# Power_Distro_Board_V6.net
KiCad netlist of a schematic drawn in EAGLE
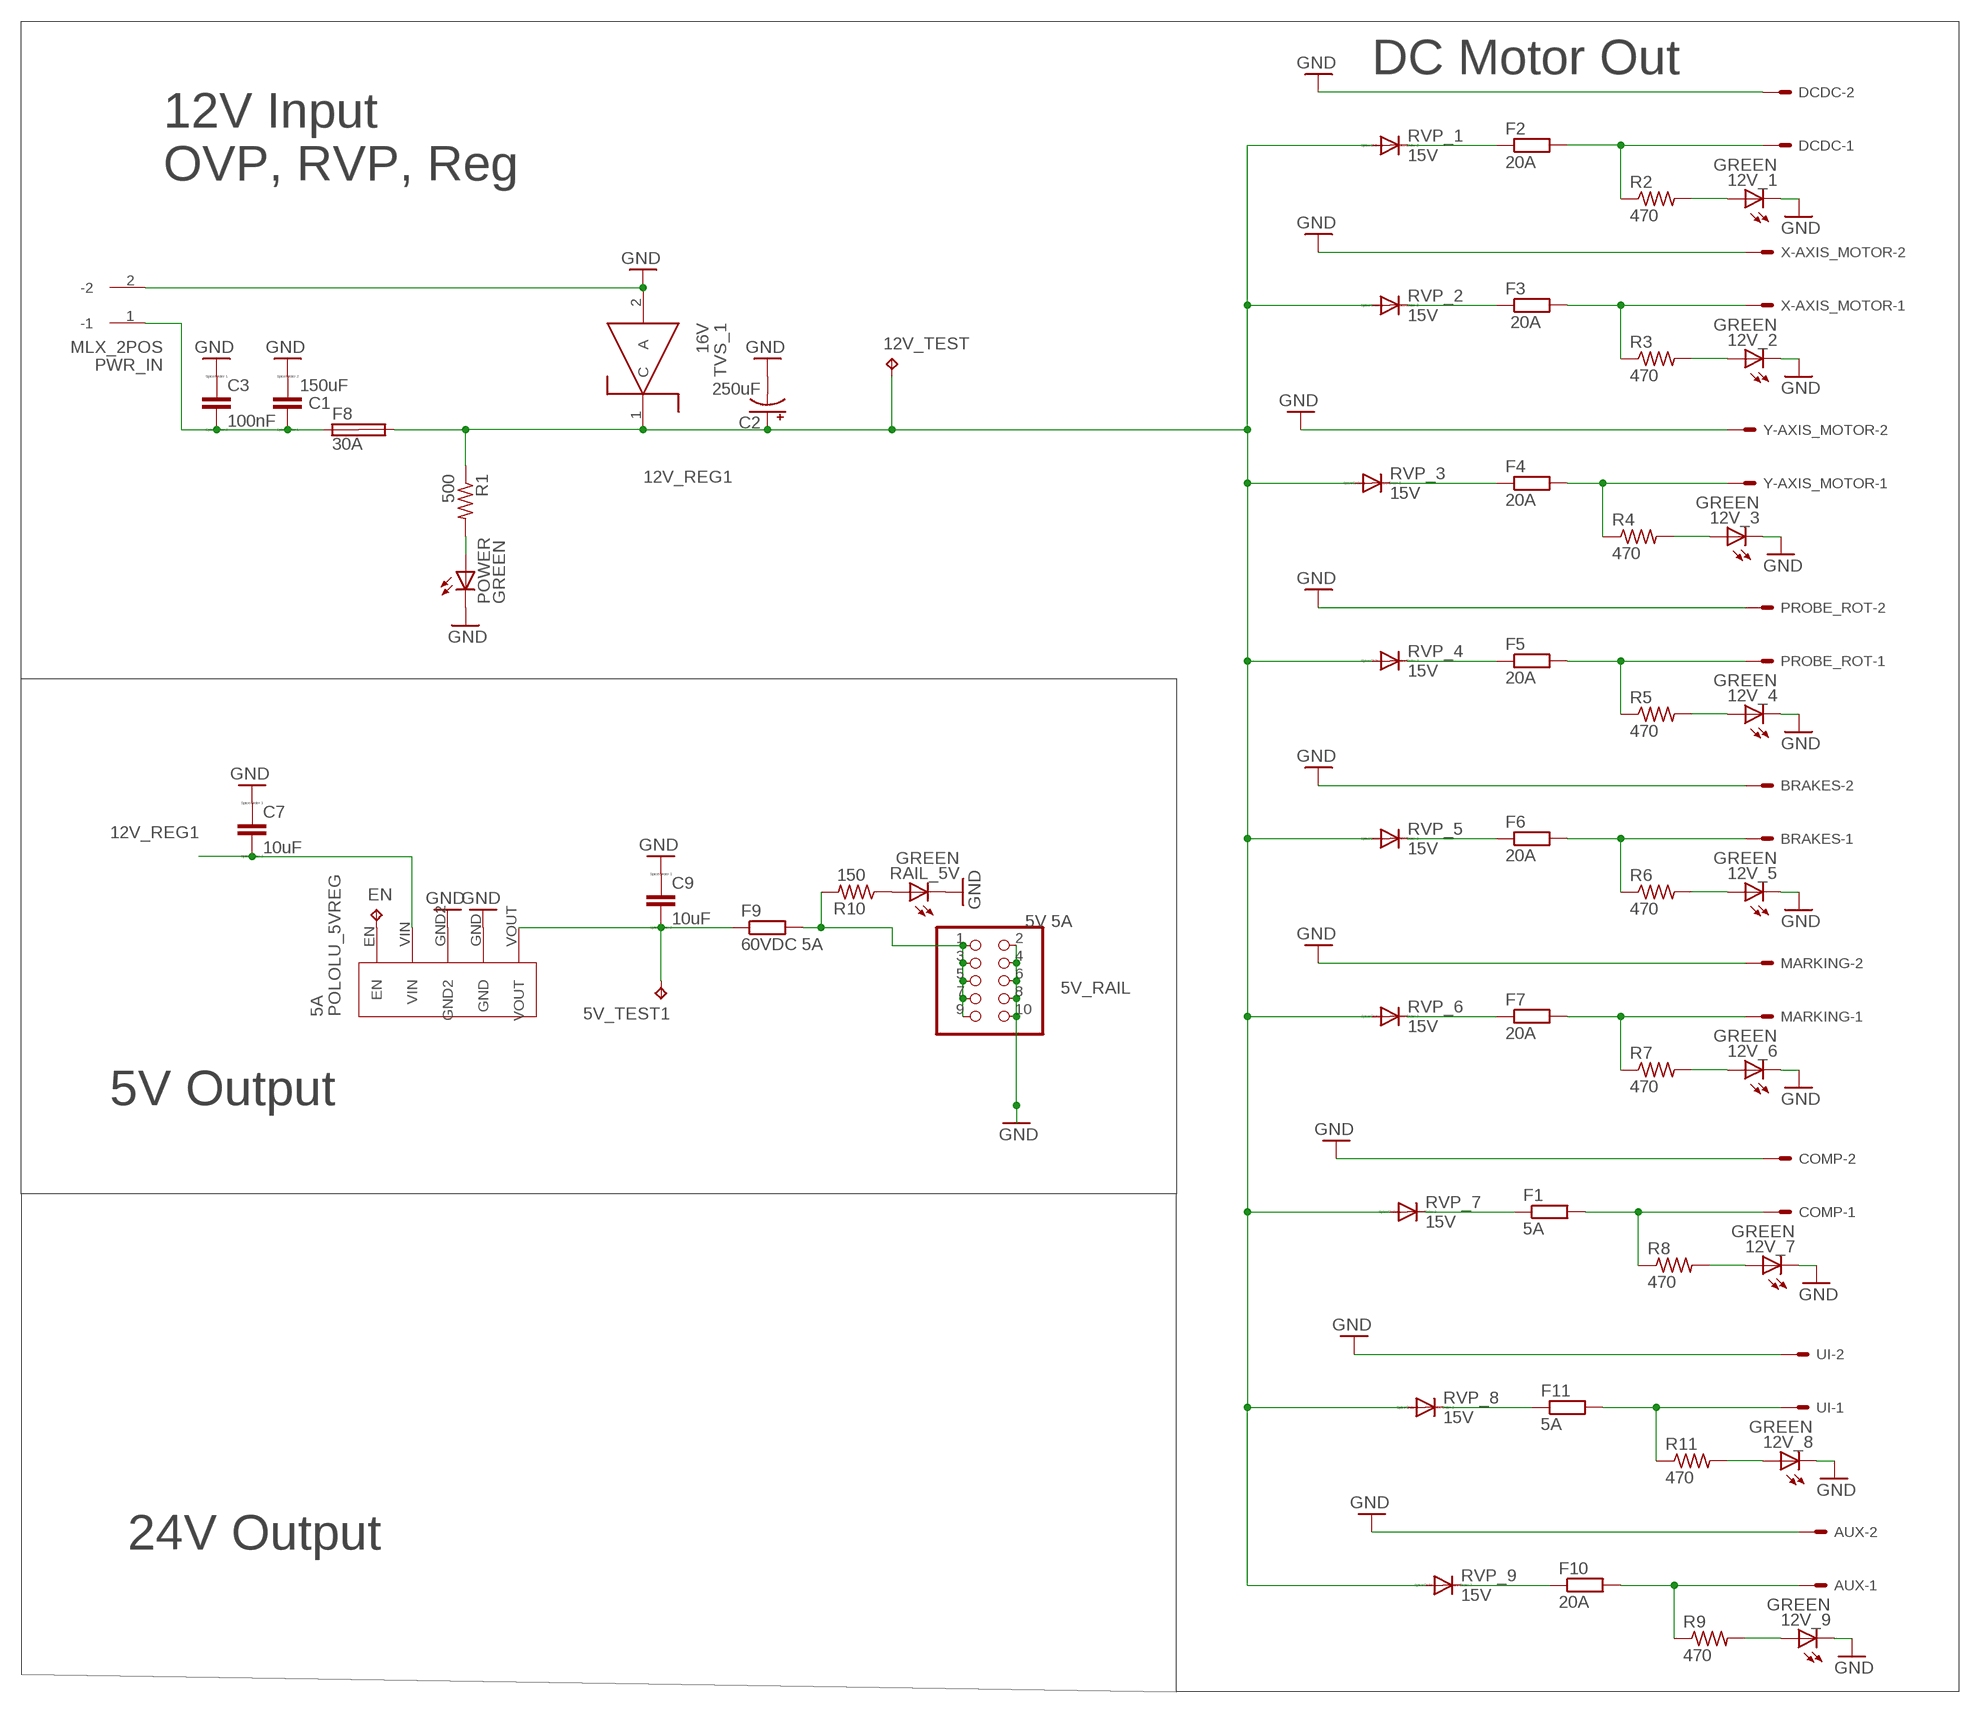
[diagram p0: schematic, sheet 1]

(export (version "E")
  (design (tool "Eeschema 10.0.6"))
  (components
    (comp (ref "5A")
      (value "POLOLU_5VREG")
      (footprint "eagle-import:SIP5")
      (libsource (lib "eagle-import") (part "POLOLU_5VREG"))
    )
    (comp (ref "5V_RAIL")
      (value "5V 5A")
      (footprint "eagle-import:2X05")
      (libsource (lib "eagle-import") (part "PINHD-2X5"))
    )
    (comp (ref "5V_TEST1")
      (value "TPPAD1-13")
      (footprint "eagle-import:P1-13")
      (libsource (lib "eagle-import") (part "TPPAD1-13"))
    )
    (comp (ref "12V_1")
      (value "GREEN")
      (footprint "eagle-import:SML1206")
      (libsource (lib "eagle-import") (part "LEDSML1206"))
    )
    (comp (ref "12V_2")
      (value "GREEN")
      (footprint "eagle-import:SML1206")
      (libsource (lib "eagle-import") (part "LEDSML1206"))
    )
    (comp (ref "12V_3")
      (value "GREEN")
      (footprint "eagle-import:SML1206")
      (libsource (lib "eagle-import") (part "LEDSML1206"))
    )
    (comp (ref "12V_4")
      (value "GREEN")
      (footprint "eagle-import:SML1206")
      (libsource (lib "eagle-import") (part "LEDSML1206"))
    )
    (comp (ref "12V_5")
      (value "GREEN")
      (footprint "eagle-import:SML1206")
      (libsource (lib "eagle-import") (part "LEDSML1206"))
    )
    (comp (ref "12V_6")
      (value "GREEN")
      (footprint "eagle-import:SML1206")
      (libsource (lib "eagle-import") (part "LEDSML1206"))
    )
    (comp (ref "12V_7")
      (value "GREEN")
      (footprint "eagle-import:SML1206")
      (libsource (lib "eagle-import") (part "LEDSML1206"))
    )
    (comp (ref "12V_8")
      (value "GREEN")
      (footprint "eagle-import:SML1206")
      (libsource (lib "eagle-import") (part "LEDSML1206"))
    )
    (comp (ref "12V_9")
      (value "GREEN")
      (footprint "eagle-import:SML1206")
      (libsource (lib "eagle-import") (part "LEDSML1206"))
    )
    (comp (ref "12V_TEST")
      (value "TPPAD1-13")
      (footprint "eagle-import:P1-13")
      (libsource (lib "eagle-import") (part "TPPAD1-13"))
    )
    (comp (ref "AUX")
      (value "555X-2V")
      (footprint "eagle-import:5566-2")
      (libsource (lib "eagle-import") (part "555X-2V"))
    )
    (comp (ref "BRAKES")
      (value "555X-2V")
      (footprint "eagle-import:5566-2")
      (libsource (lib "eagle-import") (part "555X-2V"))
    )
    (comp (ref "C1")
      (value "150uF")
      (footprint "eagle-import:C1210")
      (libsource (lib "eagle-import") (part "CC1210"))
    )
    (comp (ref "C2")
      (value "250uF")
      (footprint "eagle-import:CPOL-RADIAL-5MM-10MM")
      (libsource (lib "eagle-import") (part "ALUM_ELEC_RADIAL"))
    )
    (comp (ref "C3")
      (value "100nF")
      (footprint "eagle-import:C1210")
      (libsource (lib "eagle-import") (part "CC1210"))
    )
    (comp (ref "C7")
      (value "10uF")
      (footprint "eagle-import:C1210")
      (libsource (lib "eagle-import") (part "CC1210"))
    )
    (comp (ref "C9")
      (value "10uF")
      (footprint "eagle-import:C1210")
      (libsource (lib "eagle-import") (part "CC1210"))
    )
    (comp (ref "COMP")
      (value "555X-2V")
      (footprint "eagle-import:5566-2")
      (libsource (lib "eagle-import") (part "555X-2V"))
    )
    (comp (ref "DCDC")
      (value "555X-2V")
      (footprint "eagle-import:5566-2")
      (libsource (lib "eagle-import") (part "555X-2V"))
    )
    (comp (ref "EN")
      (value "TPPAD1-13")
      (footprint "eagle-import:P1-13")
      (libsource (lib "eagle-import") (part "TPPAD1-13"))
    )
    (comp (ref "F1")
      (value "5A")
      (footprint "eagle-import:M1206")
      (libsource (lib "eagle-import") (part "R-EU_M1206"))
    )
    (comp (ref "F2")
      (value "20A")
      (footprint "eagle-import:M1206")
      (libsource (lib "eagle-import") (part "R-EU_M1206"))
    )
    (comp (ref "F3")
      (value "20A")
      (footprint "eagle-import:M1206")
      (libsource (lib "eagle-import") (part "R-EU_M1206"))
    )
    (comp (ref "F4")
      (value "20A")
      (footprint "eagle-import:M1206")
      (libsource (lib "eagle-import") (part "R-EU_M1206"))
    )
    (comp (ref "F5")
      (value "20A")
      (footprint "eagle-import:M1206")
      (libsource (lib "eagle-import") (part "R-EU_M1206"))
    )
    (comp (ref "F6")
      (value "20A")
      (footprint "eagle-import:M1206")
      (libsource (lib "eagle-import") (part "R-EU_M1206"))
    )
    (comp (ref "F7")
      (value "20A")
      (footprint "eagle-import:M1206")
      (libsource (lib "eagle-import") (part "R-EU_M1206"))
    )
    (comp (ref "F8")
      (value "30A")
      (footprint "eagle-import:SHK20L")
      (libsource (lib "eagle-import") (part "SHK20L"))
    )
    (comp (ref "F9")
      (value "60VDC 5A")
      (footprint "eagle-import:M1206")
      (libsource (lib "eagle-import") (part "R-EU_M1206"))
    )
    (comp (ref "F10")
      (value "20A")
      (footprint "eagle-import:M1206")
      (libsource (lib "eagle-import") (part "R-EU_M1206"))
    )
    (comp (ref "F11")
      (value "5A")
      (footprint "eagle-import:M1206")
      (libsource (lib "eagle-import") (part "R-EU_M1206"))
    )
    (comp (ref "MARKING")
      (value "555X-2V")
      (footprint "eagle-import:5566-2")
      (libsource (lib "eagle-import") (part "555X-2V"))
    )
    (comp (ref "POWER")
      (value "GREEN")
      (footprint "eagle-import:SML1206")
      (libsource (lib "eagle-import") (part "LEDSML1206"))
    )
    (comp (ref "PROBE_ROT")
      (value "555X-2V")
      (footprint "eagle-import:5566-2")
      (libsource (lib "eagle-import") (part "555X-2V"))
    )
    (comp (ref "PWR_IN")
      (value "MLX_2POS")
      (footprint "eagle-import:.084MLX")
      (libsource (lib "eagle-import") (part "MLX_2POS"))
    )
    (comp (ref "R1")
      (value "500")
      (footprint "eagle-import:R1206")
      (libsource (lib "eagle-import") (part "R-US_R1206"))
    )
    (comp (ref "R2")
      (value "470")
      (footprint "eagle-import:R1206")
      (libsource (lib "eagle-import") (part "R-US_R1206"))
    )
    (comp (ref "R3")
      (value "470")
      (footprint "eagle-import:R1206")
      (libsource (lib "eagle-import") (part "R-US_R1206"))
    )
    (comp (ref "R4")
      (value "470")
      (footprint "eagle-import:R1206")
      (libsource (lib "eagle-import") (part "R-US_R1206"))
    )
    (comp (ref "R5")
      (value "470")
      (footprint "eagle-import:R1206")
      (libsource (lib "eagle-import") (part "R-US_R1206"))
    )
    (comp (ref "R6")
      (value "470")
      (footprint "eagle-import:R1206")
      (libsource (lib "eagle-import") (part "R-US_R1206"))
    )
    (comp (ref "R7")
      (value "470")
      (footprint "eagle-import:R1206")
      (libsource (lib "eagle-import") (part "R-US_R1206"))
    )
    (comp (ref "R8")
      (value "470")
      (footprint "eagle-import:R1206")
      (libsource (lib "eagle-import") (part "R-US_R1206"))
    )
    (comp (ref "R9")
      (value "470")
      (footprint "eagle-import:R1206")
      (libsource (lib "eagle-import") (part "R-US_R1206"))
    )
    (comp (ref "R10")
      (value "150")
      (footprint "eagle-import:R1206")
      (libsource (lib "eagle-import") (part "R-US_R1206"))
    )
    (comp (ref "R11")
      (value "470")
      (footprint "eagle-import:R1206")
      (libsource (lib "eagle-import") (part "R-US_R1206"))
    )
    (comp (ref "RAIL_5V")
      (value "GREEN")
      (footprint "eagle-import:SML1206")
      (libsource (lib "eagle-import") (part "LEDSML1206"))
    )
    (comp (ref "RVP_1")
      (value "15V")
      (footprint "eagle-import:TO220ACS")
      (libsource (lib "eagle-import") (part "BYT08P"))
    )
    (comp (ref "RVP_2")
      (value "15V")
      (footprint "eagle-import:TO220ACS")
      (libsource (lib "eagle-import") (part "BYT08P"))
    )
    (comp (ref "RVP_3")
      (value "15V")
      (footprint "eagle-import:TO220ACS")
      (libsource (lib "eagle-import") (part "BYT08P"))
    )
    (comp (ref "RVP_4")
      (value "15V")
      (footprint "eagle-import:TO220ACS")
      (libsource (lib "eagle-import") (part "BYT08P"))
    )
    (comp (ref "RVP_5")
      (value "15V")
      (footprint "eagle-import:TO220ACS")
      (libsource (lib "eagle-import") (part "BYT08P"))
    )
    (comp (ref "RVP_6")
      (value "15V")
      (footprint "eagle-import:TO220ACS")
      (libsource (lib "eagle-import") (part "BYT08P"))
    )
    (comp (ref "RVP_7")
      (value "15V")
      (footprint "eagle-import:TO220ACS")
      (libsource (lib "eagle-import") (part "BYT08P"))
    )
    (comp (ref "RVP_8")
      (value "15V")
      (footprint "eagle-import:TO220ACS")
      (libsource (lib "eagle-import") (part "BYT08P"))
    )
    (comp (ref "RVP_9")
      (value "15V")
      (footprint "eagle-import:TO220ACS")
      (libsource (lib "eagle-import") (part "BYT08P"))
    )
    (comp (ref "TVS_1")
      (value "16V")
      (footprint "eagle-import:DO-214AC")
      (libsource (lib "eagle-import") (part "SMAJ26A_TVSSMA"))
    )
    (comp (ref "UI")
      (value "555X-2V")
      (footprint "eagle-import:5566-2")
      (libsource (lib "eagle-import") (part "555X-2V"))
    )
    (comp (ref "X-AXIS_MOTOR")
      (value "555X-2V")
      (footprint "eagle-import:5566-2")
      (libsource (lib "eagle-import") (part "555X-2V"))
    )
    (comp (ref "Y-AXIS_MOTOR")
      (value "555X-2V")
      (footprint "eagle-import:5566-2")
      (libsource (lib "eagle-import") (part "555X-2V"))
    )
  )
  (nets
    (net (code "1") (name "/12V_REG1") (class "Default")
      (node (ref "12V_TEST") (pin "TP") (pinfunction "TP_TP") (pintype "input"))
      (node (ref "5A") (pin "VIN") (pinfunction "VIN_VIN") (pintype "bidirectional"))
      (node (ref "C2") (pin "+") (pinfunction "+_+") (pintype "passive"))
      (node (ref "C7") (pin "2") (pinfunction "2_2") (pintype "passive"))
      (node (ref "F8") (pin "2A") (pinfunction "2A_2A") (pintype "passive"))
      (node (ref "R1") (pin "1") (pinfunction "1_1") (pintype "passive"))
      (node (ref "RVP_1") (pin "A") (pinfunction "A_A") (pintype "passive"))
      (node (ref "RVP_2") (pin "A") (pinfunction "A_A") (pintype "passive"))
      (node (ref "RVP_3") (pin "A") (pinfunction "A_A") (pintype "passive"))
      (node (ref "RVP_4") (pin "A") (pinfunction "A_A") (pintype "passive"))
      (node (ref "RVP_5") (pin "A") (pinfunction "A_A") (pintype "passive"))
      (node (ref "RVP_6") (pin "A") (pinfunction "A_A") (pintype "passive"))
      (node (ref "RVP_7") (pin "A") (pinfunction "A_A") (pintype "passive"))
      (node (ref "RVP_8") (pin "A") (pinfunction "A_A") (pintype "passive"))
      (node (ref "RVP_9") (pin "A") (pinfunction "A_A") (pintype "passive"))
      (node (ref "TVS_1") (pin "1") (pinfunction "C_1") (pintype "bidirectional"))
    )
    (net (code "2") (name "GND") (class "Default")
      (node (ref "12V_1") (pin "C") (pinfunction "C_C") (pintype "passive"))
      (node (ref "12V_2") (pin "C") (pinfunction "C_C") (pintype "passive"))
      (node (ref "12V_3") (pin "C") (pinfunction "C_C") (pintype "passive"))
      (node (ref "12V_4") (pin "C") (pinfunction "C_C") (pintype "passive"))
      (node (ref "12V_5") (pin "C") (pinfunction "C_C") (pintype "passive"))
      (node (ref "12V_6") (pin "C") (pinfunction "C_C") (pintype "passive"))
      (node (ref "12V_7") (pin "C") (pinfunction "C_C") (pintype "passive"))
      (node (ref "12V_8") (pin "C") (pinfunction "C_C") (pintype "passive"))
      (node (ref "12V_9") (pin "C") (pinfunction "C_C") (pintype "passive"))
      (node (ref "5A") (pin "GND") (pinfunction "GND_GND") (pintype "bidirectional"))
      (node (ref "5A") (pin "GND2") (pinfunction "GND2_GND2") (pintype "bidirectional"))
      (node (ref "5V_RAIL") (pin "10") (pinfunction "10_10") (pintype "passive"))
      (node (ref "5V_RAIL") (pin "2") (pinfunction "2_2") (pintype "passive"))
      (node (ref "5V_RAIL") (pin "4") (pinfunction "4_4") (pintype "passive"))
      (node (ref "5V_RAIL") (pin "6") (pinfunction "6_6") (pintype "passive"))
      (node (ref "5V_RAIL") (pin "8") (pinfunction "8_8") (pintype "passive"))
      (node (ref "AUX") (pin "2") (pinfunction "S_2") (pintype "passive"))
      (node (ref "BRAKES") (pin "2") (pinfunction "S_2") (pintype "passive"))
      (node (ref "C1") (pin "2") (pinfunction "2_2") (pintype "passive"))
      (node (ref "C2") (pin "-") (pinfunction "-_-") (pintype "passive"))
      (node (ref "C3") (pin "1") (pinfunction "1_1") (pintype "passive"))
      (node (ref "C7") (pin "1") (pinfunction "1_1") (pintype "passive"))
      (node (ref "C9") (pin "1") (pinfunction "1_1") (pintype "passive"))
      (node (ref "COMP") (pin "2") (pinfunction "S_2") (pintype "passive"))
      (node (ref "DCDC") (pin "2") (pinfunction "S_2") (pintype "passive"))
      (node (ref "MARKING") (pin "2") (pinfunction "S_2") (pintype "passive"))
      (node (ref "POWER") (pin "C") (pinfunction "C_C") (pintype "passive"))
      (node (ref "PROBE_ROT") (pin "2") (pinfunction "S_2") (pintype "passive"))
      (node (ref "PWR_IN") (pin "2") (pinfunction "-2_2") (pintype "bidirectional"))
      (node (ref "RAIL_5V") (pin "C") (pinfunction "C_C") (pintype "passive"))
      (node (ref "TVS_1") (pin "2") (pinfunction "A_2") (pintype "bidirectional"))
      (node (ref "UI") (pin "2") (pinfunction "S_2") (pintype "passive"))
      (node (ref "X-AXIS_MOTOR") (pin "2") (pinfunction "S_2") (pintype "passive"))
      (node (ref "Y-AXIS_MOTOR") (pin "2") (pinfunction "S_2") (pintype "passive"))
    )
    (net (code "3") (name "Net-(5A-PadEN)") (class "Default")
      (node (ref "5A") (pin "EN") (pinfunction "EN_EN") (pintype "bidirectional"))
      (node (ref "EN") (pin "TP") (pinfunction "TP_TP") (pintype "input"))
    )
    (net (code "4") (name "Net-(5A-PadVOUT)") (class "Default")
      (node (ref "5A") (pin "VOUT") (pinfunction "VOUT_VOUT") (pintype "bidirectional"))
      (node (ref "5V_TEST1") (pin "TP") (pinfunction "TP_TP") (pintype "input"))
      (node (ref "C9") (pin "2") (pinfunction "2_2") (pintype "passive"))
      (node (ref "F9") (pin "1") (pinfunction "1_1") (pintype "passive"))
    )
    (net (code "5") (name "Net-(5V_RAIL-Pad1)") (class "Default")
      (node (ref "5V_RAIL") (pin "1") (pinfunction "1_1") (pintype "passive"))
      (node (ref "5V_RAIL") (pin "3") (pinfunction "3_3") (pintype "passive"))
      (node (ref "5V_RAIL") (pin "5") (pinfunction "5_5") (pintype "passive"))
      (node (ref "5V_RAIL") (pin "7") (pinfunction "7_7") (pintype "passive"))
      (node (ref "5V_RAIL") (pin "9") (pinfunction "9_9") (pintype "passive"))
      (node (ref "F9") (pin "2") (pinfunction "2_2") (pintype "passive"))
      (node (ref "R10") (pin "2") (pinfunction "2_2") (pintype "passive"))
    )
    (net (code "6") (name "Net-(12V_1-PadA)") (class "Default")
      (node (ref "12V_1") (pin "A") (pinfunction "A_A") (pintype "passive"))
      (node (ref "R2") (pin "2") (pinfunction "2_2") (pintype "passive"))
    )
    (net (code "7") (name "Net-(12V_2-PadA)") (class "Default")
      (node (ref "12V_2") (pin "A") (pinfunction "A_A") (pintype "passive"))
      (node (ref "R3") (pin "2") (pinfunction "2_2") (pintype "passive"))
    )
    (net (code "8") (name "Net-(12V_3-PadA)") (class "Default")
      (node (ref "12V_3") (pin "A") (pinfunction "A_A") (pintype "passive"))
      (node (ref "R4") (pin "2") (pinfunction "2_2") (pintype "passive"))
    )
    (net (code "9") (name "Net-(12V_4-PadA)") (class "Default")
      (node (ref "12V_4") (pin "A") (pinfunction "A_A") (pintype "passive"))
      (node (ref "R5") (pin "2") (pinfunction "2_2") (pintype "passive"))
    )
    (net (code "10") (name "Net-(12V_5-PadA)") (class "Default")
      (node (ref "12V_5") (pin "A") (pinfunction "A_A") (pintype "passive"))
      (node (ref "R6") (pin "2") (pinfunction "2_2") (pintype "passive"))
    )
    (net (code "11") (name "Net-(12V_6-PadA)") (class "Default")
      (node (ref "12V_6") (pin "A") (pinfunction "A_A") (pintype "passive"))
      (node (ref "R7") (pin "2") (pinfunction "2_2") (pintype "passive"))
    )
    (net (code "12") (name "Net-(12V_7-PadA)") (class "Default")
      (node (ref "12V_7") (pin "A") (pinfunction "A_A") (pintype "passive"))
      (node (ref "R8") (pin "2") (pinfunction "2_2") (pintype "passive"))
    )
    (net (code "13") (name "Net-(12V_8-PadA)") (class "Default")
      (node (ref "12V_8") (pin "A") (pinfunction "A_A") (pintype "passive"))
      (node (ref "R11") (pin "2") (pinfunction "2_2") (pintype "passive"))
    )
    (net (code "14") (name "Net-(12V_9-PadA)") (class "Default")
      (node (ref "12V_9") (pin "A") (pinfunction "A_A") (pintype "passive"))
      (node (ref "R9") (pin "2") (pinfunction "2_2") (pintype "passive"))
    )
    (net (code "15") (name "Net-(AUXA-S)") (class "Default")
      (node (ref "AUX") (pin "1") (pinfunction "S_1") (pintype "passive"))
      (node (ref "F10") (pin "2") (pinfunction "2_2") (pintype "passive"))
      (node (ref "R9") (pin "1") (pinfunction "1_1") (pintype "passive"))
    )
    (net (code "16") (name "Net-(BRAKESA-S)") (class "Default")
      (node (ref "BRAKES") (pin "1") (pinfunction "S_1") (pintype "passive"))
      (node (ref "F6") (pin "2") (pinfunction "2_2") (pintype "passive"))
      (node (ref "R6") (pin "1") (pinfunction "1_1") (pintype "passive"))
    )
    (net (code "17") (name "Net-(COMPA-S)") (class "Default")
      (node (ref "COMP") (pin "1") (pinfunction "S_1") (pintype "passive"))
      (node (ref "F1") (pin "2") (pinfunction "2_2") (pintype "passive"))
      (node (ref "R8") (pin "1") (pinfunction "1_1") (pintype "passive"))
    )
    (net (code "18") (name "Net-(DCDCA-S)") (class "Default")
      (node (ref "DCDC") (pin "1") (pinfunction "S_1") (pintype "passive"))
      (node (ref "F2") (pin "2") (pinfunction "2_2") (pintype "passive"))
      (node (ref "R2") (pin "1") (pinfunction "1_1") (pintype "passive"))
    )
    (net (code "19") (name "Net-(F1-Pad1)") (class "Default")
      (node (ref "F1") (pin "1") (pinfunction "1_1") (pintype "passive"))
      (node (ref "RVP_7") (pin "C") (pinfunction "C_C") (pintype "passive"))
    )
    (net (code "20") (name "Net-(F2-Pad1)") (class "Default")
      (node (ref "F2") (pin "1") (pinfunction "1_1") (pintype "passive"))
      (node (ref "RVP_1") (pin "C") (pinfunction "C_C") (pintype "passive"))
    )
    (net (code "21") (name "Net-(F3-Pad1)") (class "Default")
      (node (ref "F3") (pin "1") (pinfunction "1_1") (pintype "passive"))
      (node (ref "RVP_2") (pin "C") (pinfunction "C_C") (pintype "passive"))
    )
    (net (code "22") (name "Net-(F4-Pad1)") (class "Default")
      (node (ref "F4") (pin "1") (pinfunction "1_1") (pintype "passive"))
      (node (ref "RVP_3") (pin "C") (pinfunction "C_C") (pintype "passive"))
    )
    (net (code "23") (name "Net-(F5-Pad1)") (class "Default")
      (node (ref "F5") (pin "1") (pinfunction "1_1") (pintype "passive"))
      (node (ref "RVP_4") (pin "C") (pinfunction "C_C") (pintype "passive"))
    )
    (net (code "24") (name "Net-(F6-Pad1)") (class "Default")
      (node (ref "F6") (pin "1") (pinfunction "1_1") (pintype "passive"))
      (node (ref "RVP_5") (pin "C") (pinfunction "C_C") (pintype "passive"))
    )
    (net (code "25") (name "Net-(F7-Pad1)") (class "Default")
      (node (ref "F7") (pin "1") (pinfunction "1_1") (pintype "passive"))
      (node (ref "RVP_6") (pin "C") (pinfunction "C_C") (pintype "passive"))
    )
    (net (code "26") (name "Net-(F10-Pad1)") (class "Default")
      (node (ref "F10") (pin "1") (pinfunction "1_1") (pintype "passive"))
      (node (ref "RVP_9") (pin "C") (pinfunction "C_C") (pintype "passive"))
    )
    (net (code "27") (name "Net-(F11-Pad1)") (class "Default")
      (node (ref "F11") (pin "1") (pinfunction "1_1") (pintype "passive"))
      (node (ref "RVP_8") (pin "C") (pinfunction "C_C") (pintype "passive"))
    )
    (net (code "28") (name "Net-(MARKINGA-S)") (class "Default")
      (node (ref "F7") (pin "2") (pinfunction "2_2") (pintype "passive"))
      (node (ref "MARKING") (pin "1") (pinfunction "S_1") (pintype "passive"))
      (node (ref "R7") (pin "1") (pinfunction "1_1") (pintype "passive"))
    )
    (net (code "29") (name "Net-(POWER-PadA)") (class "Default")
      (node (ref "POWER") (pin "A") (pinfunction "A_A") (pintype "passive"))
      (node (ref "R1") (pin "2") (pinfunction "2_2") (pintype "passive"))
    )
    (net (code "30") (name "Net-(PROBE_ROTA-S)") (class "Default")
      (node (ref "F5") (pin "2") (pinfunction "2_2") (pintype "passive"))
      (node (ref "PROBE_ROT") (pin "1") (pinfunction "S_1") (pintype "passive"))
      (node (ref "R5") (pin "1") (pinfunction "1_1") (pintype "passive"))
    )
    (net (code "31") (name "Net-(PWR_IN--1)") (class "Default")
      (node (ref "C1") (pin "1") (pinfunction "1_1") (pintype "passive"))
      (node (ref "C3") (pin "2") (pinfunction "2_2") (pintype "passive"))
      (node (ref "F8") (pin "1A") (pinfunction "1A_1A") (pintype "passive"))
      (node (ref "PWR_IN") (pin "1") (pinfunction "-1_1") (pintype "bidirectional"))
    )
    (net (code "32") (name "Net-(R10-Pad1)") (class "Default")
      (node (ref "R10") (pin "1") (pinfunction "1_1") (pintype "passive"))
      (node (ref "RAIL_5V") (pin "A") (pinfunction "A_A") (pintype "passive"))
    )
    (net (code "33") (name "Net-(UIA-S)") (class "Default")
      (node (ref "F11") (pin "2") (pinfunction "2_2") (pintype "passive"))
      (node (ref "R11") (pin "1") (pinfunction "1_1") (pintype "passive"))
      (node (ref "UI") (pin "1") (pinfunction "S_1") (pintype "passive"))
    )
    (net (code "34") (name "Net-(X-AXIS_MOTORA-S)") (class "Default")
      (node (ref "F3") (pin "2") (pinfunction "2_2") (pintype "passive"))
      (node (ref "R3") (pin "1") (pinfunction "1_1") (pintype "passive"))
      (node (ref "X-AXIS_MOTOR") (pin "1") (pinfunction "S_1") (pintype "passive"))
    )
    (net (code "35") (name "Net-(Y-AXIS_MOTORA-S)") (class "Default")
      (node (ref "F4") (pin "2") (pinfunction "2_2") (pintype "passive"))
      (node (ref "R4") (pin "1") (pinfunction "1_1") (pintype "passive"))
      (node (ref "Y-AXIS_MOTOR") (pin "1") (pinfunction "S_1") (pintype "passive"))
    )
    (net (code "36") (name "unconnected-(F8-Pad1B)") (class "Default")
      (node (ref "F8") (pin "1B") (pinfunction "1B_1B") (pintype "passive"))
    )
    (net (code "37") (name "unconnected-(F8-Pad2B)") (class "Default")
      (node (ref "F8") (pin "2B") (pinfunction "2B_2B") (pintype "passive"))
    )
  )
)
